# FeatherwingCircuit.net
KiCad netlist of a schematic drawn in EAGLE
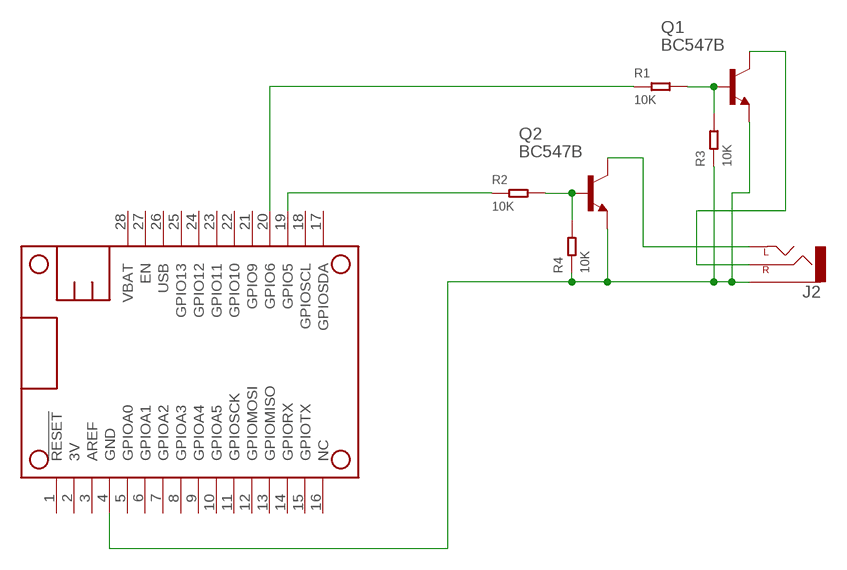
[diagram p0: schematic, sheet 1]

(export (version "E")
  (design (tool "Eeschema 10.0.6"))
  (components
    (comp (ref "J2")
      (value "AUDIO_JACK_2.5MM_2.5MM")
      (footprint "eagle-import:STEREOJACK2.5MM_STEREOJACK2.5MM")
      (libsource (lib "eagle-import") (part "AUDIO_JACK_2.5MM_2.5MM"))
    )
    (comp (ref "MS1")
      (value "FEATHERWING_NODIM")
      (footprint "eagle-import:FEATHERWING_DIM")
      (libsource (lib "eagle-import") (part "FEATHERWING_NODIM"))
    )
    (comp (ref "Q1")
      (value "BC547B")
      (footprint "eagle-import:TO92")
      (libsource (lib "eagle-import") (part "BC547B"))
    )
    (comp (ref "Q2")
      (value "BC547B")
      (footprint "eagle-import:TO92")
      (libsource (lib "eagle-import") (part "BC547B"))
    )
    (comp (ref "R1")
      (value "10K")
      (footprint "eagle-import:PR-D2.3XL6.5MM")
      (fields (field (name "MPN") "FHCFR-1/4W-103J"))
      (libsource (lib "eagle-import") (part "DIP-RES-10K-5%-1/4W(PR-D2.3XL6.5MM)"))
    )
    (comp (ref "R2")
      (value "10K")
      (footprint "eagle-import:PR-D2.3XL6.5MM")
      (fields (field (name "MPN") "FHCFR-1/4W-103J"))
      (libsource (lib "eagle-import") (part "DIP-RES-10K-5%-1/4W(PR-D2.3XL6.5MM)"))
    )
    (comp (ref "R3")
      (value "10K")
      (footprint "eagle-import:PR-D2.3XL6.5MM")
      (fields (field (name "MPN") "FHCFR-1/4W-103J"))
      (libsource (lib "eagle-import") (part "DIP-RES-10K-5%-1/4W(PR-D2.3XL6.5MM)"))
    )
    (comp (ref "R4")
      (value "10K")
      (footprint "eagle-import:PR-D2.3XL6.5MM")
      (fields (field (name "MPN") "FHCFR-1/4W-103J"))
      (libsource (lib "eagle-import") (part "DIP-RES-10K-5%-1/4W(PR-D2.3XL6.5MM)"))
    )
  )
  (nets
    (net (code "1") (name "/3V") (class "Default")
      (node (ref "MS1") (pin "2") (pinfunction "3V_2") (pintype "power_in"))
    )
    (net (code "2") (name "/USB") (class "Default")
      (node (ref "MS1") (pin "26") (pinfunction "USB_26") (pintype "power_in"))
    )
    (net (code "3") (name "/VBAT") (class "Default")
      (node (ref "MS1") (pin "28") (pinfunction "VBAT_28") (pintype "power_in"))
    )
    (net (code "4") (name "Net-(J2-LEFT)") (class "Default")
      (node (ref "J2") (pin "SHIELD") (pinfunction "LEFT_SHIELD") (pintype "bidirectional"))
      (node (ref "Q2") (pin "3") (pinfunction "C_3") (pintype "passive"))
    )
    (net (code "5") (name "Net-(J2-RIGHT)") (class "Default")
      (node (ref "J2") (pin "TIP") (pinfunction "RIGHT_TIP") (pintype "bidirectional"))
      (node (ref "Q1") (pin "3") (pinfunction "C_3") (pintype "passive"))
    )
    (net (code "6") (name "Net-(J2-SLEEVE)") (class "Default")
      (node (ref "J2") (pin "RING1") (pinfunction "SLEEVE_RING1") (pintype "bidirectional"))
      (node (ref "MS1") (pin "4") (pinfunction "GND_4") (pintype "power_in"))
      (node (ref "Q1") (pin "1") (pinfunction "E_1") (pintype "passive"))
      (node (ref "Q2") (pin "1") (pinfunction "E_1") (pintype "passive"))
      (node (ref "R3") (pin "1") (pinfunction "1_1") (pintype "passive"))
      (node (ref "R4") (pin "1") (pinfunction "1_1") (pintype "passive"))
    )
    (net (code "7") (name "Net-(MS1-GPIO5)") (class "Default")
      (node (ref "MS1") (pin "19") (pinfunction "GPIO5_19") (pintype "bidirectional"))
      (node (ref "R2") (pin "1") (pinfunction "1_1") (pintype "passive"))
    )
    (net (code "8") (name "Net-(MS1-GPIO6)") (class "Default")
      (node (ref "MS1") (pin "20") (pinfunction "GPIO6_20") (pintype "bidirectional"))
      (node (ref "R1") (pin "1") (pinfunction "1_1") (pintype "passive"))
    )
    (net (code "9") (name "Net-(Q1-B)") (class "Default")
      (node (ref "Q1") (pin "2") (pinfunction "B_2") (pintype "passive"))
      (node (ref "R1") (pin "2") (pinfunction "2_2") (pintype "passive"))
      (node (ref "R3") (pin "2") (pinfunction "2_2") (pintype "passive"))
    )
    (net (code "10") (name "Net-(Q2-B)") (class "Default")
      (node (ref "Q2") (pin "2") (pinfunction "B_2") (pintype "passive"))
      (node (ref "R2") (pin "2") (pinfunction "2_2") (pintype "passive"))
      (node (ref "R4") (pin "2") (pinfunction "2_2") (pintype "passive"))
    )
    (net (code "11") (name "unconnected-(MS1-AREF-Pad3)") (class "Default")
      (node (ref "MS1") (pin "3") (pinfunction "AREF_3") (pintype "passive"))
    )
    (net (code "12") (name "unconnected-(MS1-EN-Pad27)") (class "Default")
      (node (ref "MS1") (pin "27") (pinfunction "EN_27") (pintype "passive"))
    )
    (net (code "13") (name "unconnected-(MS1-GPIO9-Pad21)") (class "Default")
      (node (ref "MS1") (pin "21") (pinfunction "GPIO9_21") (pintype "bidirectional"))
    )
    (net (code "14") (name "unconnected-(MS1-GPIO10-Pad22)") (class "Default")
      (node (ref "MS1") (pin "22") (pinfunction "GPIO10_22") (pintype "bidirectional"))
    )
    (net (code "15") (name "unconnected-(MS1-GPIO11-Pad23)") (class "Default")
      (node (ref "MS1") (pin "23") (pinfunction "GPIO11_23") (pintype "bidirectional"))
    )
    (net (code "16") (name "unconnected-(MS1-GPIO12-Pad24)") (class "Default")
      (node (ref "MS1") (pin "24") (pinfunction "GPIO12_24") (pintype "bidirectional"))
    )
    (net (code "17") (name "unconnected-(MS1-GPIO13-Pad25)") (class "Default")
      (node (ref "MS1") (pin "25") (pinfunction "GPIO13_25") (pintype "bidirectional"))
    )
    (net (code "18") (name "unconnected-(MS1-GPIOA0-Pad5)") (class "Default")
      (node (ref "MS1") (pin "5") (pinfunction "GPIOA0_5") (pintype "bidirectional"))
    )
    (net (code "19") (name "unconnected-(MS1-GPIOA1-Pad6)") (class "Default")
      (node (ref "MS1") (pin "6") (pinfunction "GPIOA1_6") (pintype "bidirectional"))
    )
    (net (code "20") (name "unconnected-(MS1-GPIOA2-Pad7)") (class "Default")
      (node (ref "MS1") (pin "7") (pinfunction "GPIOA2_7") (pintype "bidirectional"))
    )
    (net (code "21") (name "unconnected-(MS1-GPIOA3-Pad8)") (class "Default")
      (node (ref "MS1") (pin "8") (pinfunction "GPIOA3_8") (pintype "bidirectional"))
    )
    (net (code "22") (name "unconnected-(MS1-GPIOA4-Pad9)") (class "Default")
      (node (ref "MS1") (pin "9") (pinfunction "GPIOA4_9") (pintype "bidirectional"))
    )
    (net (code "23") (name "unconnected-(MS1-GPIOA5-Pad10)") (class "Default")
      (node (ref "MS1") (pin "10") (pinfunction "GPIOA5_10") (pintype "bidirectional"))
    )
    (net (code "24") (name "unconnected-(MS1-GPIOMISO-Pad13)") (class "Default")
      (node (ref "MS1") (pin "13") (pinfunction "GPIOMISO_13") (pintype "bidirectional"))
    )
    (net (code "25") (name "unconnected-(MS1-GPIOMOSI-Pad12)") (class "Default")
      (node (ref "MS1") (pin "12") (pinfunction "GPIOMOSI_12") (pintype "bidirectional"))
    )
    (net (code "26") (name "unconnected-(MS1-GPIORX-Pad14)") (class "Default")
      (node (ref "MS1") (pin "14") (pinfunction "GPIORX_14") (pintype "bidirectional"))
    )
    (net (code "27") (name "unconnected-(MS1-GPIOSCK-Pad11)") (class "Default")
      (node (ref "MS1") (pin "11") (pinfunction "GPIOSCK_11") (pintype "bidirectional"))
    )
    (net (code "28") (name "unconnected-(MS1-GPIOSCL-Pad18)") (class "Default")
      (node (ref "MS1") (pin "18") (pinfunction "GPIOSCL_18") (pintype "bidirectional"))
    )
    (net (code "29") (name "unconnected-(MS1-GPIOSDA-Pad17)") (class "Default")
      (node (ref "MS1") (pin "17") (pinfunction "GPIOSDA_17") (pintype "bidirectional"))
    )
    (net (code "30") (name "unconnected-(MS1-GPIOTX-Pad15)") (class "Default")
      (node (ref "MS1") (pin "15") (pinfunction "GPIOTX_15") (pintype "bidirectional"))
    )
    (net (code "31") (name "unconnected-(MS1-NC-Pad16)") (class "Default")
      (node (ref "MS1") (pin "16") (pinfunction "NC_16") (pintype "passive"))
    )
    (net (code "32") (name "unconnected-(MS1-~{RESET}-Pad1)") (class "Default")
      (node (ref "MS1") (pin "1") (pinfunction "~{RESET}_1") (pintype "input"))
    )
  )
)
